# M632X.net
KiCad netlist of a schematic drawn in EAGLE
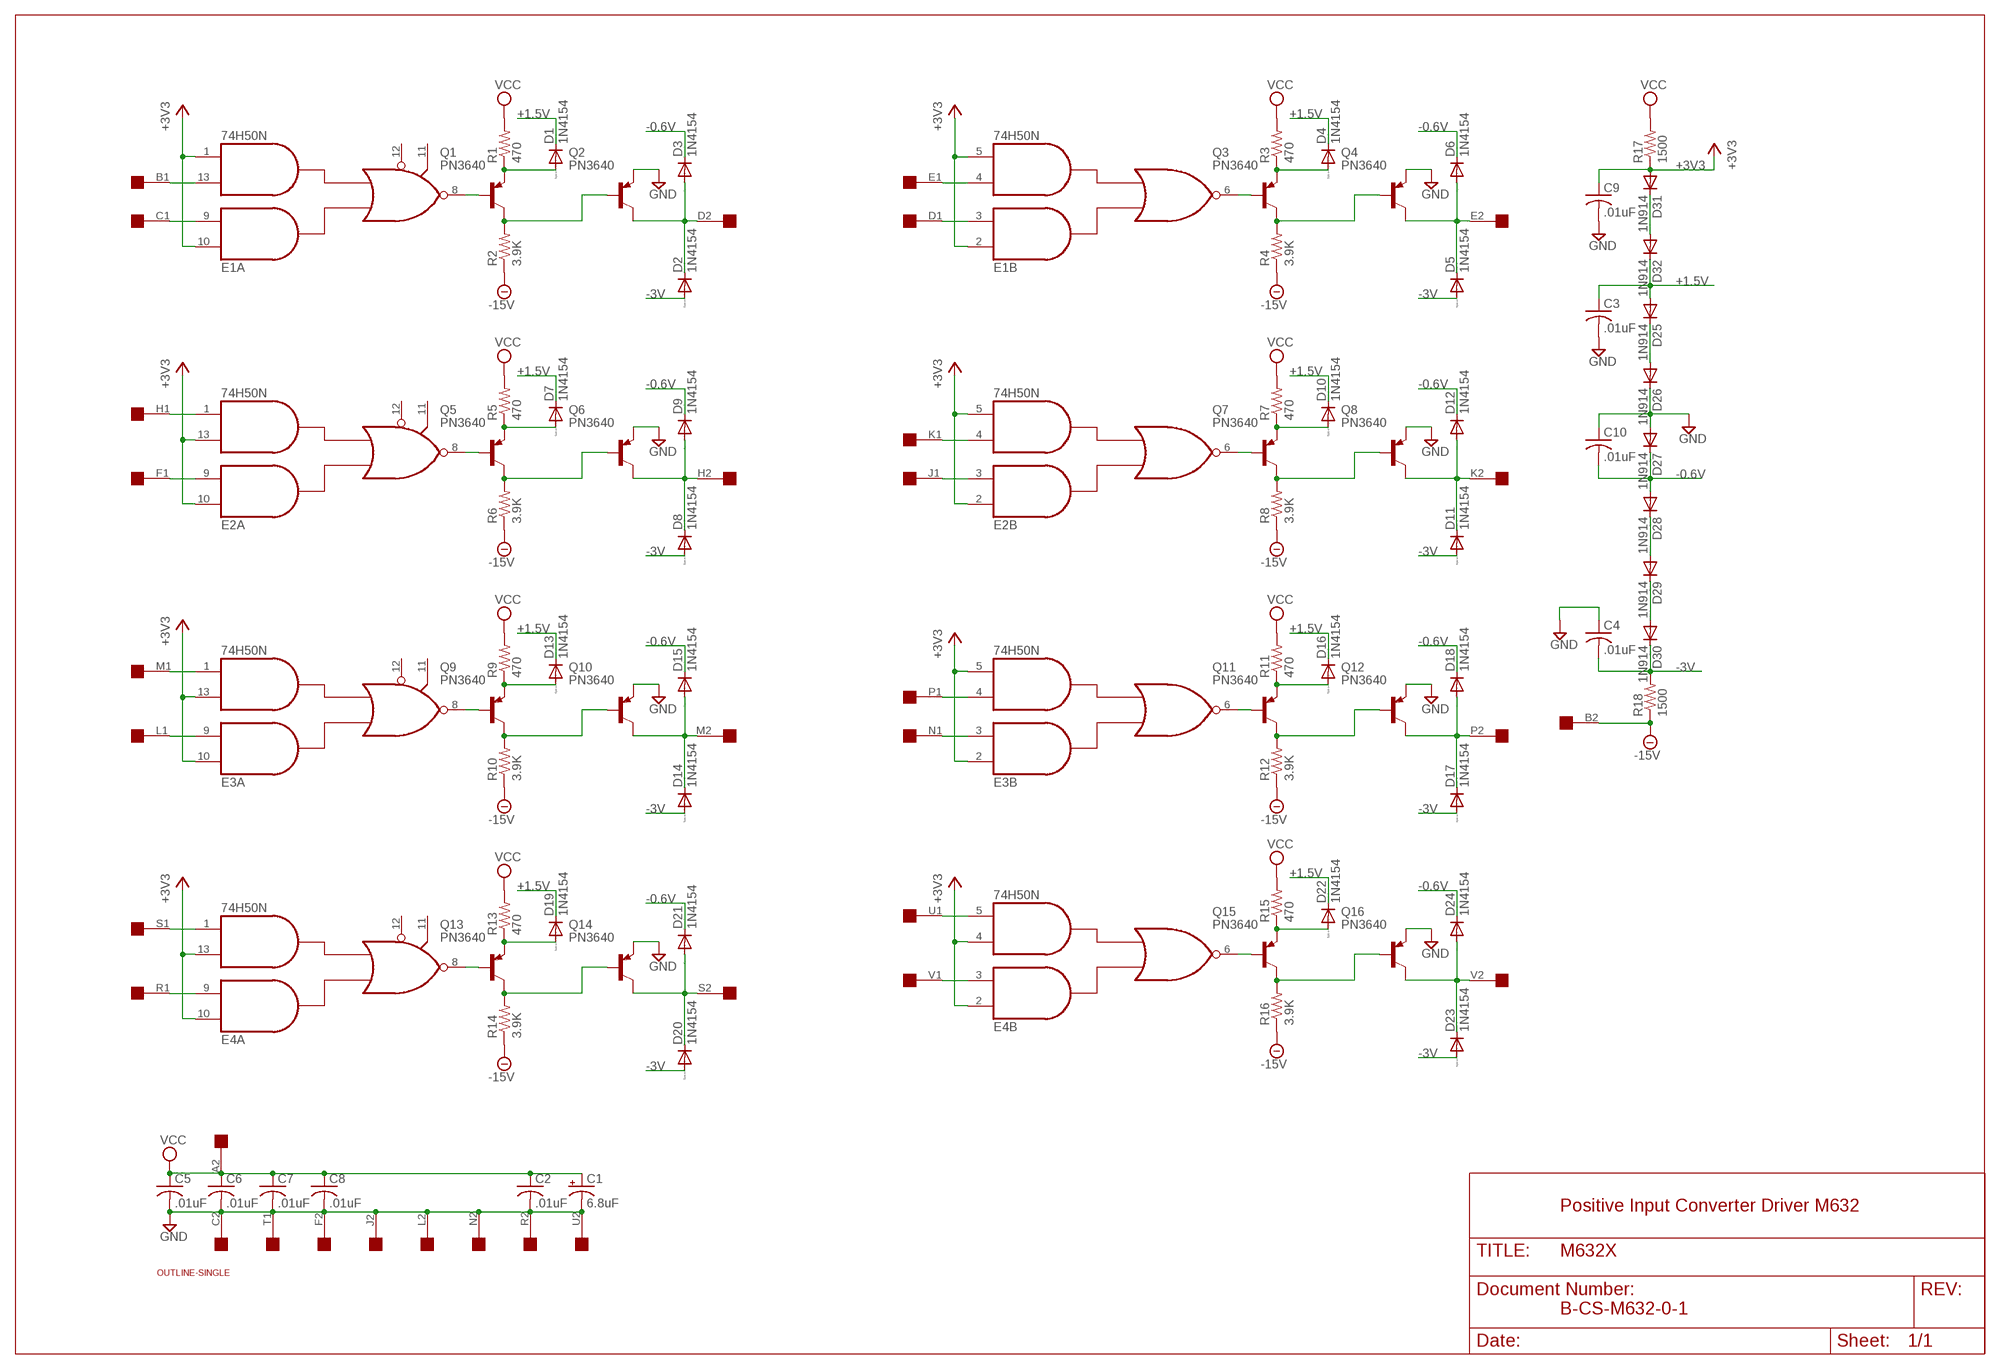
[diagram p0: schematic, sheet 1]

(export (version "E")
  (design (tool "Eeschema 10.0.6"))
  (components
    (comp (ref "C1")
      (value "6.8uF")
      (footprint "eagle-import:E12-8")
      (libsource (lib "eagle-import") (part "CPOL-USE20-8AXIAL"))
    )
    (comp (ref "C2")
      (value ".01uF")
      (footprint "eagle-import:C050-025X075")
      (libsource (lib "eagle-import") (part "C-US050-025X075"))
    )
    (comp (ref "C3")
      (value ".01uF")
      (footprint "eagle-import:C050-025X075")
      (libsource (lib "eagle-import") (part "C-US050-025X075"))
    )
    (comp (ref "C4")
      (value ".01uF")
      (footprint "eagle-import:C050-025X075")
      (libsource (lib "eagle-import") (part "C-US050-025X075"))
    )
    (comp (ref "C5")
      (value ".01uF")
      (footprint "eagle-import:C050-025X075")
      (libsource (lib "eagle-import") (part "C-US050-025X075"))
    )
    (comp (ref "C6")
      (value ".01uF")
      (footprint "eagle-import:C050-025X075")
      (libsource (lib "eagle-import") (part "C-US050-025X075"))
    )
    (comp (ref "C7")
      (value ".01uF")
      (footprint "eagle-import:C050-025X075")
      (libsource (lib "eagle-import") (part "C-US050-025X075"))
    )
    (comp (ref "C8")
      (value ".01uF")
      (footprint "eagle-import:C050-025X075")
      (libsource (lib "eagle-import") (part "C-US050-025X075"))
    )
    (comp (ref "C9")
      (value ".01uF")
      (footprint "eagle-import:C050-025X075")
      (libsource (lib "eagle-import") (part "C-US050-025X075"))
    )
    (comp (ref "C10")
      (value ".01uF")
      (footprint "eagle-import:C050-025X075")
      (libsource (lib "eagle-import") (part "C-US050-025X075"))
    )
    (comp (ref "D1")
      (value "1N4154")
      (footprint "eagle-import:DO35-10")
      (libsource (lib "eagle-import") (part "1N4148DO35-10"))
    )
    (comp (ref "D2")
      (value "1N4154")
      (footprint "eagle-import:DO35-10")
      (libsource (lib "eagle-import") (part "1N4148DO35-10"))
    )
    (comp (ref "D3")
      (value "1N4154")
      (footprint "eagle-import:DO35-10")
      (libsource (lib "eagle-import") (part "1N4148DO35-10"))
    )
    (comp (ref "D4")
      (value "1N4154")
      (footprint "eagle-import:DO35-10")
      (libsource (lib "eagle-import") (part "1N4148DO35-10"))
    )
    (comp (ref "D5")
      (value "1N4154")
      (footprint "eagle-import:DO35-10")
      (libsource (lib "eagle-import") (part "1N4148DO35-10"))
    )
    (comp (ref "D6")
      (value "1N4154")
      (footprint "eagle-import:DO35-10")
      (libsource (lib "eagle-import") (part "1N4148DO35-10"))
    )
    (comp (ref "D7")
      (value "1N4154")
      (footprint "eagle-import:DO35-10")
      (libsource (lib "eagle-import") (part "1N4148DO35-10"))
    )
    (comp (ref "D8")
      (value "1N4154")
      (footprint "eagle-import:DO35-10")
      (libsource (lib "eagle-import") (part "1N4148DO35-10"))
    )
    (comp (ref "D9")
      (value "1N4154")
      (footprint "eagle-import:DO35-10")
      (libsource (lib "eagle-import") (part "1N4148DO35-10"))
    )
    (comp (ref "D10")
      (value "1N4154")
      (footprint "eagle-import:DO35-10")
      (libsource (lib "eagle-import") (part "1N4148DO35-10"))
    )
    (comp (ref "D11")
      (value "1N4154")
      (footprint "eagle-import:DO35-10")
      (libsource (lib "eagle-import") (part "1N4148DO35-10"))
    )
    (comp (ref "D12")
      (value "1N4154")
      (footprint "eagle-import:DO35-10")
      (libsource (lib "eagle-import") (part "1N4148DO35-10"))
    )
    (comp (ref "D13")
      (value "1N4154")
      (footprint "eagle-import:DO35-10")
      (libsource (lib "eagle-import") (part "1N4148DO35-10"))
    )
    (comp (ref "D14")
      (value "1N4154")
      (footprint "eagle-import:DO35-10")
      (libsource (lib "eagle-import") (part "1N4148DO35-10"))
    )
    (comp (ref "D15")
      (value "1N4154")
      (footprint "eagle-import:DO35-10")
      (libsource (lib "eagle-import") (part "1N4148DO35-10"))
    )
    (comp (ref "D16")
      (value "1N4154")
      (footprint "eagle-import:DO35-10")
      (libsource (lib "eagle-import") (part "1N4148DO35-10"))
    )
    (comp (ref "D17")
      (value "1N4154")
      (footprint "eagle-import:DO35-10")
      (libsource (lib "eagle-import") (part "1N4148DO35-10"))
    )
    (comp (ref "D18")
      (value "1N4154")
      (footprint "eagle-import:DO35-10")
      (libsource (lib "eagle-import") (part "1N4148DO35-10"))
    )
    (comp (ref "D19")
      (value "1N4154")
      (footprint "eagle-import:DO35-10")
      (libsource (lib "eagle-import") (part "1N4148DO35-10"))
    )
    (comp (ref "D20")
      (value "1N4154")
      (footprint "eagle-import:DO35-10")
      (libsource (lib "eagle-import") (part "1N4148DO35-10"))
    )
    (comp (ref "D21")
      (value "1N4154")
      (footprint "eagle-import:DO35-10")
      (libsource (lib "eagle-import") (part "1N4148DO35-10"))
    )
    (comp (ref "D22")
      (value "1N4154")
      (footprint "eagle-import:DO35-10")
      (libsource (lib "eagle-import") (part "1N4148DO35-10"))
    )
    (comp (ref "D23")
      (value "1N4154")
      (footprint "eagle-import:DO35-10")
      (libsource (lib "eagle-import") (part "1N4148DO35-10"))
    )
    (comp (ref "D24")
      (value "1N4154")
      (footprint "eagle-import:DO35-10")
      (libsource (lib "eagle-import") (part "1N4148DO35-10"))
    )
    (comp (ref "D25")
      (value "1N914")
      (footprint "eagle-import:DO35-10")
      (libsource (lib "eagle-import") (part "1N4148DO35-10"))
    )
    (comp (ref "D26")
      (value "1N914")
      (footprint "eagle-import:DO35-10")
      (libsource (lib "eagle-import") (part "1N4148DO35-10"))
    )
    (comp (ref "D27")
      (value "1N914")
      (footprint "eagle-import:DO35-10")
      (libsource (lib "eagle-import") (part "1N4148DO35-10"))
    )
    (comp (ref "D28")
      (value "1N914")
      (footprint "eagle-import:DO35-10")
      (libsource (lib "eagle-import") (part "1N4148DO35-10"))
    )
    (comp (ref "D29")
      (value "1N914")
      (footprint "eagle-import:DO35-10")
      (libsource (lib "eagle-import") (part "1N4148DO35-10"))
    )
    (comp (ref "D30")
      (value "1N914")
      (footprint "eagle-import:DO35-10")
      (libsource (lib "eagle-import") (part "1N4148DO35-10"))
    )
    (comp (ref "D31")
      (value "1N914")
      (footprint "eagle-import:DO35-10")
      (libsource (lib "eagle-import") (part "1N4148DO35-10"))
    )
    (comp (ref "D32")
      (value "1N914")
      (footprint "eagle-import:DO35-10")
      (libsource (lib "eagle-import") (part "1N4148DO35-10"))
    )
    (comp (ref "E1")
      (value "74H50N")
      (footprint "eagle-import:DIL14")
      (libsource (lib "eagle-import") (part "7450N"))
    )
    (comp (ref "E2")
      (value "74H50N")
      (footprint "eagle-import:DIL14")
      (libsource (lib "eagle-import") (part "7450N"))
    )
    (comp (ref "E3")
      (value "74H50N")
      (footprint "eagle-import:DIL14")
      (libsource (lib "eagle-import") (part "7450N"))
    )
    (comp (ref "E4")
      (value "74H50N")
      (footprint "eagle-import:DIL14")
      (libsource (lib "eagle-import") (part "7450N"))
    )
    (comp (ref "Q1")
      (value "PN3640")
      (footprint "eagle-import:TO39")
      (libsource (lib "eagle-import") (part "2N2904"))
    )
    (comp (ref "Q2")
      (value "PN3640")
      (footprint "eagle-import:TO39")
      (libsource (lib "eagle-import") (part "2N2904"))
    )
    (comp (ref "Q3")
      (value "PN3640")
      (footprint "eagle-import:TO39")
      (libsource (lib "eagle-import") (part "2N2904"))
    )
    (comp (ref "Q4")
      (value "PN3640")
      (footprint "eagle-import:TO39")
      (libsource (lib "eagle-import") (part "2N2904"))
    )
    (comp (ref "Q5")
      (value "PN3640")
      (footprint "eagle-import:TO39")
      (libsource (lib "eagle-import") (part "2N2904"))
    )
    (comp (ref "Q6")
      (value "PN3640")
      (footprint "eagle-import:TO39")
      (libsource (lib "eagle-import") (part "2N2904"))
    )
    (comp (ref "Q7")
      (value "PN3640")
      (footprint "eagle-import:TO39")
      (libsource (lib "eagle-import") (part "2N2904"))
    )
    (comp (ref "Q8")
      (value "PN3640")
      (footprint "eagle-import:TO39")
      (libsource (lib "eagle-import") (part "2N2904"))
    )
    (comp (ref "Q9")
      (value "PN3640")
      (footprint "eagle-import:TO39")
      (libsource (lib "eagle-import") (part "2N2904"))
    )
    (comp (ref "Q10")
      (value "PN3640")
      (footprint "eagle-import:TO39")
      (libsource (lib "eagle-import") (part "2N2904"))
    )
    (comp (ref "Q11")
      (value "PN3640")
      (footprint "eagle-import:TO39")
      (libsource (lib "eagle-import") (part "2N2904"))
    )
    (comp (ref "Q12")
      (value "PN3640")
      (footprint "eagle-import:TO39")
      (libsource (lib "eagle-import") (part "2N2904"))
    )
    (comp (ref "Q13")
      (value "PN3640")
      (footprint "eagle-import:TO39")
      (libsource (lib "eagle-import") (part "2N2904"))
    )
    (comp (ref "Q14")
      (value "PN3640")
      (footprint "eagle-import:TO39")
      (libsource (lib "eagle-import") (part "2N2904"))
    )
    (comp (ref "Q15")
      (value "PN3640")
      (footprint "eagle-import:TO39")
      (libsource (lib "eagle-import") (part "2N2904"))
    )
    (comp (ref "Q16")
      (value "PN3640")
      (footprint "eagle-import:TO39")
      (libsource (lib "eagle-import") (part "2N2904"))
    )
    (comp (ref "R1")
      (value "470")
      (footprint "eagle-import:0207_10")
      (libsource (lib "eagle-import") (part "R-US_0207/10"))
    )
    (comp (ref "R2")
      (value "3.9K")
      (footprint "eagle-import:0207_10")
      (libsource (lib "eagle-import") (part "R-US_0207/10"))
    )
    (comp (ref "R3")
      (value "470")
      (footprint "eagle-import:0207_10")
      (libsource (lib "eagle-import") (part "R-US_0207/10"))
    )
    (comp (ref "R4")
      (value "3.9K")
      (footprint "eagle-import:0207_10")
      (libsource (lib "eagle-import") (part "R-US_0207/10"))
    )
    (comp (ref "R5")
      (value "470")
      (footprint "eagle-import:0207_10")
      (libsource (lib "eagle-import") (part "R-US_0207/10"))
    )
    (comp (ref "R6")
      (value "3.9K")
      (footprint "eagle-import:0207_10")
      (libsource (lib "eagle-import") (part "R-US_0207/10"))
    )
    (comp (ref "R7")
      (value "470")
      (footprint "eagle-import:0207_10")
      (libsource (lib "eagle-import") (part "R-US_0207/10"))
    )
    (comp (ref "R8")
      (value "3.9K")
      (footprint "eagle-import:0207_10")
      (libsource (lib "eagle-import") (part "R-US_0207/10"))
    )
    (comp (ref "R9")
      (value "470")
      (footprint "eagle-import:0207_10")
      (libsource (lib "eagle-import") (part "R-US_0207/10"))
    )
    (comp (ref "R10")
      (value "3.9K")
      (footprint "eagle-import:0207_10")
      (libsource (lib "eagle-import") (part "R-US_0207/10"))
    )
    (comp (ref "R11")
      (value "470")
      (footprint "eagle-import:0207_10")
      (libsource (lib "eagle-import") (part "R-US_0207/10"))
    )
    (comp (ref "R12")
      (value "3.9K")
      (footprint "eagle-import:0207_10")
      (libsource (lib "eagle-import") (part "R-US_0207/10"))
    )
    (comp (ref "R13")
      (value "470")
      (footprint "eagle-import:0207_10")
      (libsource (lib "eagle-import") (part "R-US_0207/10"))
    )
    (comp (ref "R14")
      (value "3.9K")
      (footprint "eagle-import:0207_10")
      (libsource (lib "eagle-import") (part "R-US_0207/10"))
    )
    (comp (ref "R15")
      (value "470")
      (footprint "eagle-import:0207_10")
      (libsource (lib "eagle-import") (part "R-US_0207/10"))
    )
    (comp (ref "R16")
      (value "3.9K")
      (footprint "eagle-import:0207_10")
      (libsource (lib "eagle-import") (part "R-US_0207/10"))
    )
    (comp (ref "R17")
      (value "1500")
      (footprint "eagle-import:0207_10")
      (libsource (lib "eagle-import") (part "R-US_0207/10"))
    )
    (comp (ref "R18")
      (value "1500")
      (footprint "eagle-import:0207_10")
      (libsource (lib "eagle-import") (part "R-US_0207/10"))
    )
    (comp (ref "U$1")
      (value "SINGLE")
      (footprint "eagle-import:EDGE-CON2")
      (libsource (lib "eagle-import") (part "SINGLE"))
    )
    (comp (ref "U$4")
      (value "OUTLINE-SINGLE")
      (footprint "eagle-import:SINGLE")
      (libsource (lib "eagle-import") (part "OUTLINE-SINGLE"))
    )
  )
  (nets
    (net (code "1") (name "+3V3") (class "Default")
      (node (ref "C9") (pin "1") (pinfunction "1_1") (pintype "passive"))
      (node (ref "D31") (pin "A") (pinfunction "A_A") (pintype "passive"))
      (node (ref "E1") (pin "1") (pinfunction "I4_1") (pintype "input"))
      (node (ref "E1") (pin "10") (pinfunction "I1_10") (pintype "input"))
      (node (ref "E1") (pin "2") (pinfunction "I1_2") (pintype "input"))
      (node (ref "E1") (pin "5") (pinfunction "I4_5") (pintype "input"))
      (node (ref "E2") (pin "10") (pinfunction "I1_10") (pintype "input"))
      (node (ref "E2") (pin "13") (pinfunction "I3_13") (pintype "input"))
      (node (ref "E2") (pin "2") (pinfunction "I1_2") (pintype "input"))
      (node (ref "E2") (pin "5") (pinfunction "I4_5") (pintype "input"))
      (node (ref "E3") (pin "10") (pinfunction "I1_10") (pintype "input"))
      (node (ref "E3") (pin "13") (pinfunction "I3_13") (pintype "input"))
      (node (ref "E3") (pin "2") (pinfunction "I1_2") (pintype "input"))
      (node (ref "E3") (pin "5") (pinfunction "I4_5") (pintype "input"))
      (node (ref "E4") (pin "10") (pinfunction "I1_10") (pintype "input"))
      (node (ref "E4") (pin "13") (pinfunction "I3_13") (pintype "input"))
      (node (ref "E4") (pin "2") (pinfunction "I1_2") (pintype "input"))
      (node (ref "E4") (pin "4") (pinfunction "I3_4") (pintype "input"))
      (node (ref "R17") (pin "1") (pinfunction "1_1") (pintype "passive"))
    )
    (net (code "2") (name "-15V") (class "Default")
      (node (ref "R10") (pin "1") (pinfunction "1_1") (pintype "passive"))
      (node (ref "R12") (pin "1") (pinfunction "1_1") (pintype "passive"))
      (node (ref "R14") (pin "1") (pinfunction "1_1") (pintype "passive"))
      (node (ref "R16") (pin "1") (pinfunction "1_1") (pintype "passive"))
      (node (ref "R18") (pin "1") (pinfunction "1_1") (pintype "passive"))
      (node (ref "R2") (pin "1") (pinfunction "1_1") (pintype "passive"))
      (node (ref "R4") (pin "1") (pinfunction "1_1") (pintype "passive"))
      (node (ref "R6") (pin "1") (pinfunction "1_1") (pintype "passive"))
      (node (ref "R8") (pin "1") (pinfunction "1_1") (pintype "passive"))
      (node (ref "U$1") (pin "B2") (pinfunction "1_B2") (pintype "bidirectional"))
    )
    (net (code "3") (name "/+1.5V") (class "Default")
      (node (ref "C3") (pin "1") (pinfunction "1_1") (pintype "passive"))
      (node (ref "D1") (pin "C") (pinfunction "C_C") (pintype "passive"))
      (node (ref "D10") (pin "C") (pinfunction "C_C") (pintype "passive"))
      (node (ref "D13") (pin "C") (pinfunction "C_C") (pintype "passive"))
      (node (ref "D16") (pin "C") (pinfunction "C_C") (pintype "passive"))
      (node (ref "D19") (pin "C") (pinfunction "C_C") (pintype "passive"))
      (node (ref "D22") (pin "C") (pinfunction "C_C") (pintype "passive"))
      (node (ref "D25") (pin "A") (pinfunction "A_A") (pintype "passive"))
      (node (ref "D32") (pin "C") (pinfunction "C_C") (pintype "passive"))
      (node (ref "D4") (pin "C") (pinfunction "C_C") (pintype "passive"))
      (node (ref "D7") (pin "C") (pinfunction "C_C") (pintype "passive"))
    )
    (net (code "4") (name "/-0.6V") (class "Default")
      (node (ref "C10") (pin "2") (pinfunction "2_2") (pintype "passive"))
      (node (ref "D12") (pin "C") (pinfunction "C_C") (pintype "passive"))
      (node (ref "D15") (pin "C") (pinfunction "C_C") (pintype "passive"))
      (node (ref "D18") (pin "C") (pinfunction "C_C") (pintype "passive"))
      (node (ref "D21") (pin "C") (pinfunction "C_C") (pintype "passive"))
      (node (ref "D24") (pin "C") (pinfunction "C_C") (pintype "passive"))
      (node (ref "D27") (pin "C") (pinfunction "C_C") (pintype "passive"))
      (node (ref "D28") (pin "A") (pinfunction "A_A") (pintype "passive"))
      (node (ref "D3") (pin "C") (pinfunction "C_C") (pintype "passive"))
      (node (ref "D6") (pin "C") (pinfunction "C_C") (pintype "passive"))
      (node (ref "D9") (pin "C") (pinfunction "C_C") (pintype "passive"))
    )
    (net (code "5") (name "/-3V") (class "Default")
      (node (ref "C4") (pin "2") (pinfunction "2_2") (pintype "passive"))
      (node (ref "D11") (pin "A") (pinfunction "A_A") (pintype "passive"))
      (node (ref "D14") (pin "A") (pinfunction "A_A") (pintype "passive"))
      (node (ref "D17") (pin "A") (pinfunction "A_A") (pintype "passive"))
      (node (ref "D2") (pin "A") (pinfunction "A_A") (pintype "passive"))
      (node (ref "D20") (pin "A") (pinfunction "A_A") (pintype "passive"))
      (node (ref "D23") (pin "A") (pinfunction "A_A") (pintype "passive"))
      (node (ref "D30") (pin "C") (pinfunction "C_C") (pintype "passive"))
      (node (ref "D5") (pin "A") (pinfunction "A_A") (pintype "passive"))
      (node (ref "D8") (pin "A") (pinfunction "A_A") (pintype "passive"))
      (node (ref "R18") (pin "2") (pinfunction "2_2") (pintype "passive"))
    )
    (net (code "6") (name "GND") (class "Default")
      (node (ref "C1") (pin "-") (pinfunction "-_-") (pintype "passive"))
      (node (ref "C10") (pin "1") (pinfunction "1_1") (pintype "passive"))
      (node (ref "C2") (pin "2") (pinfunction "2_2") (pintype "passive"))
      (node (ref "C3") (pin "2") (pinfunction "2_2") (pintype "passive"))
      (node (ref "C4") (pin "1") (pinfunction "1_1") (pintype "passive"))
      (node (ref "C5") (pin "2") (pinfunction "2_2") (pintype "passive"))
      (node (ref "C6") (pin "2") (pinfunction "2_2") (pintype "passive"))
      (node (ref "C7") (pin "2") (pinfunction "2_2") (pintype "passive"))
      (node (ref "C8") (pin "2") (pinfunction "2_2") (pintype "passive"))
      (node (ref "C9") (pin "2") (pinfunction "2_2") (pintype "passive"))
      (node (ref "D26") (pin "C") (pinfunction "C_C") (pintype "passive"))
      (node (ref "D27") (pin "A") (pinfunction "A_A") (pintype "passive"))
      (node (ref "Q10") (pin "1") (pinfunction "E_1") (pintype "passive"))
      (node (ref "Q12") (pin "1") (pinfunction "E_1") (pintype "passive"))
      (node (ref "Q14") (pin "1") (pinfunction "E_1") (pintype "passive"))
      (node (ref "Q16") (pin "1") (pinfunction "E_1") (pintype "passive"))
      (node (ref "Q2") (pin "1") (pinfunction "E_1") (pintype "passive"))
      (node (ref "Q4") (pin "1") (pinfunction "E_1") (pintype "passive"))
      (node (ref "Q6") (pin "1") (pinfunction "E_1") (pintype "passive"))
      (node (ref "Q8") (pin "1") (pinfunction "E_1") (pintype "passive"))
      (node (ref "U$1") (pin "C2") (pinfunction "1_C2") (pintype "bidirectional"))
      (node (ref "U$1") (pin "F2") (pinfunction "1_F2") (pintype "bidirectional"))
      (node (ref "U$1") (pin "J2") (pinfunction "1_J2") (pintype "bidirectional"))
      (node (ref "U$1") (pin "L2") (pinfunction "1_L2") (pintype "bidirectional"))
      (node (ref "U$1") (pin "N2") (pinfunction "1_N2") (pintype "bidirectional"))
      (node (ref "U$1") (pin "R2") (pinfunction "1_R2") (pintype "bidirectional"))
      (node (ref "U$1") (pin "T1") (pinfunction "1_T1") (pintype "bidirectional"))
      (node (ref "U$1") (pin "U2") (pinfunction "1_U2") (pintype "bidirectional"))
    )
    (net (code "7") (name "Net-(D25-PadC)") (class "Default")
      (node (ref "D25") (pin "C") (pinfunction "C_C") (pintype "passive"))
      (node (ref "D26") (pin "A") (pinfunction "A_A") (pintype "passive"))
    )
    (net (code "8") (name "Net-(D28-PadC)") (class "Default")
      (node (ref "D28") (pin "C") (pinfunction "C_C") (pintype "passive"))
      (node (ref "D29") (pin "A") (pinfunction "A_A") (pintype "passive"))
    )
    (net (code "9") (name "Net-(D29-PadC)") (class "Default")
      (node (ref "D29") (pin "C") (pinfunction "C_C") (pintype "passive"))
      (node (ref "D30") (pin "A") (pinfunction "A_A") (pintype "passive"))
    )
    (net (code "10") (name "Net-(D31-PadC)") (class "Default")
      (node (ref "D31") (pin "C") (pinfunction "C_C") (pintype "passive"))
      (node (ref "D32") (pin "A") (pinfunction "A_A") (pintype "passive"))
    )
    (net (code "11") (name "Net-(E1A-I2)") (class "Default")
      (node (ref "E1") (pin "9") (pinfunction "I2_9") (pintype "input"))
      (node (ref "U$1") (pin "C1") (pinfunction "1_C1") (pintype "bidirectional"))
    )
    (net (code "12") (name "Net-(E1A-I3)") (class "Default")
      (node (ref "E1") (pin "13") (pinfunction "I3_13") (pintype "input"))
      (node (ref "U$1") (pin "B1") (pinfunction "1_B1") (pintype "bidirectional"))
    )
    (net (code "13") (name "Net-(E1A-O)") (class "Default")
      (node (ref "E1") (pin "8") (pinfunction "O_8") (pintype "output"))
      (node (ref "Q1") (pin "2") (pinfunction "B_2") (pintype "passive"))
    )
    (net (code "14") (name "Net-(E1B-I2)") (class "Default")
      (node (ref "E1") (pin "3") (pinfunction "I2_3") (pintype "input"))
      (node (ref "U$1") (pin "D1") (pinfunction "1_D1") (pintype "bidirectional"))
    )
    (net (code "15") (name "Net-(E1B-I3)") (class "Default")
      (node (ref "E1") (pin "4") (pinfunction "I3_4") (pintype "input"))
      (node (ref "U$1") (pin "E1") (pinfunction "1_E1") (pintype "bidirectional"))
    )
    (net (code "16") (name "Net-(E1B-O)") (class "Default")
      (node (ref "E1") (pin "6") (pinfunction "O_6") (pintype "output"))
      (node (ref "Q3") (pin "2") (pinfunction "B_2") (pintype "passive"))
    )
    (net (code "17") (name "Net-(E2A-I2)") (class "Default")
      (node (ref "E2") (pin "9") (pinfunction "I2_9") (pintype "input"))
      (node (ref "U$1") (pin "F1") (pinfunction "1_F1") (pintype "bidirectional"))
    )
    (net (code "18") (name "Net-(E2A-I4)") (class "Default")
      (node (ref "E2") (pin "1") (pinfunction "I4_1") (pintype "input"))
      (node (ref "U$1") (pin "H1") (pinfunction "1_H1") (pintype "bidirectional"))
    )
    (net (code "19") (name "Net-(E2A-O)") (class "Default")
      (node (ref "E2") (pin "8") (pinfunction "O_8") (pintype "output"))
      (node (ref "Q5") (pin "2") (pinfunction "B_2") (pintype "passive"))
    )
    (net (code "20") (name "Net-(E2B-I2)") (class "Default")
      (node (ref "E2") (pin "3") (pinfunction "I2_3") (pintype "input"))
      (node (ref "U$1") (pin "J1") (pinfunction "1_J1") (pintype "bidirectional"))
    )
    (net (code "21") (name "Net-(E2B-I3)") (class "Default")
      (node (ref "E2") (pin "4") (pinfunction "I3_4") (pintype "input"))
      (node (ref "U$1") (pin "K1") (pinfunction "1_K1") (pintype "bidirectional"))
    )
    (net (code "22") (name "Net-(E2B-O)") (class "Default")
      (node (ref "E2") (pin "6") (pinfunction "O_6") (pintype "output"))
      (node (ref "Q7") (pin "2") (pinfunction "B_2") (pintype "passive"))
    )
    (net (code "23") (name "Net-(E3A-I2)") (class "Default")
      (node (ref "E3") (pin "9") (pinfunction "I2_9") (pintype "input"))
      (node (ref "U$1") (pin "L1") (pinfunction "1_L1") (pintype "bidirectional"))
    )
    (net (code "24") (name "Net-(E3A-I4)") (class "Default")
      (node (ref "E3") (pin "1") (pinfunction "I4_1") (pintype "input"))
      (node (ref "U$1") (pin "M1") (pinfunction "1_M1") (pintype "bidirectional"))
    )
    (net (code "25") (name "Net-(E3A-O)") (class "Default")
      (node (ref "E3") (pin "8") (pinfunction "O_8") (pintype "output"))
      (node (ref "Q9") (pin "2") (pinfunction "B_2") (pintype "passive"))
    )
    (net (code "26") (name "Net-(E3B-I2)") (class "Default")
      (node (ref "E3") (pin "3") (pinfunction "I2_3") (pintype "input"))
      (node (ref "U$1") (pin "N1") (pinfunction "1_N1") (pintype "bidirectional"))
    )
    (net (code "27") (name "Net-(E3B-I3)") (class "Default")
      (node (ref "E3") (pin "4") (pinfunction "I3_4") (pintype "input"))
      (node (ref "U$1") (pin "P1") (pinfunction "1_P1") (pintype "bidirectional"))
    )
    (net (code "28") (name "Net-(E3B-O)") (class "Default")
      (node (ref "E3") (pin "6") (pinfunction "O_6") (pintype "output"))
      (node (ref "Q11") (pin "2") (pinfunction "B_2") (pintype "passive"))
    )
    (net (code "29") (name "Net-(E4A-I2)") (class "Default")
      (node (ref "E4") (pin "9") (pinfunction "I2_9") (pintype "input"))
      (node (ref "U$1") (pin "R1") (pinfunction "1_R1") (pintype "bidirectional"))
    )
    (net (code "30") (name "Net-(E4A-I4)") (class "Default")
      (node (ref "E4") (pin "1") (pinfunction "I4_1") (pintype "input"))
      (node (ref "U$1") (pin "S1") (pinfunction "1_S1") (pintype "bidirectional"))
    )
    (net (code "31") (name "Net-(E4A-O)") (class "Default")
      (node (ref "E4") (pin "8") (pinfunction "O_8") (pintype "output"))
      (node (ref "Q13") (pin "2") (pinfunction "B_2") (pintype "passive"))
    )
    (net (code "32") (name "Net-(E4B-I2)") (class "Default")
      (node (ref "E4") (pin "3") (pinfunction "I2_3") (pintype "input"))
      (node (ref "U$1") (pin "V1") (pinfunction "1_V1") (pintype "bidirectional"))
    )
    (net (code "33") (name "Net-(E4B-I4)") (class "Default")
      (node (ref "E4") (pin "5") (pinfunction "I4_5") (pintype "input"))
      (node (ref "U$1") (pin "U1") (pinfunction "1_U1") (pintype "bidirectional"))
    )
    (net (code "34") (name "Net-(E4B-O)") (class "Default")
      (node (ref "E4") (pin "6") (pinfunction "O_6") (pintype "output"))
      (node (ref "Q15") (pin "2") (pinfunction "B_2") (pintype "passive"))
    )
    (net (code "35") (name "Net-(Q1-C)") (class "Default")
      (node (ref "Q1") (pin "3") (pinfunction "C_3") (pintype "passive"))
      (node (ref "Q2") (pin "2") (pinfunction "B_2") (pintype "passive"))
      (node (ref "R2") (pin "2") (pinfunction "2_2") (pintype "passive"))
    )
    (net (code "36") (name "Net-(Q1-E)") (class "Default")
      (node (ref "D1") (pin "A") (pinfunction "A_A") (pintype "passive"))
      (node (ref "Q1") (pin "1") (pinfunction "E_1") (pintype "passive"))
      (node (ref "R1") (pin "1") (pinfunction "1_1") (pintype "passive"))
    )
    (net (code "37") (name "Net-(Q2-C)") (class "Default")
      (node (ref "D2") (pin "C") (pinfunction "C_C") (pintype "passive"))
      (node (ref "D3") (pin "A") (pinfunction "A_A") (pintype "passive"))
      (node (ref "Q2") (pin "3") (pinfunction "C_3") (pintype "passive"))
      (node (ref "U$1") (pin "D2") (pinfunction "1_D2") (pintype "bidirectional"))
    )
    (net (code "38") (name "Net-(Q3-C)") (class "Default")
      (node (ref "Q3") (pin "3") (pinfunction "C_3") (pintype "passive"))
      (node (ref "Q4") (pin "2") (pinfunction "B_2") (pintype "passive"))
      (node (ref "R4") (pin "2") (pinfunction "2_2") (pintype "passive"))
    )
    (net (code "39") (name "Net-(Q3-E)") (class "Default")
      (node (ref "D4") (pin "A") (pinfunction "A_A") (pintype "passive"))
      (node (ref "Q3") (pin "1") (pinfunction "E_1") (pintype "passive"))
      (node (ref "R3") (pin "1") (pinfunction "1_1") (pintype "passive"))
    )
    (net (code "40") (name "Net-(Q4-C)") (class "Default")
      (node (ref "D5") (pin "C") (pinfunction "C_C") (pintype "passive"))
      (node (ref "D6") (pin "A") (pinfunction "A_A") (pintype "passive"))
      (node (ref "Q4") (pin "3") (pinfunction "C_3") (pintype "passive"))
      (node (ref "U$1") (pin "E2") (pinfunction "1_E2") (pintype "bidirectional"))
    )
    (net (code "41") (name "Net-(Q5-C)") (class "Default")
      (node (ref "Q5") (pin "3") (pinfunction "C_3") (pintype "passive"))
      (node (ref "Q6") (pin "2") (pinfunction "B_2") (pintype "passive"))
      (node (ref "R6") (pin "2") (pinfunction "2_2") (pintype "passive"))
    )
    (net (code "42") (name "Net-(Q5-E)") (class "Default")
      (node (ref "D7") (pin "A") (pinfunction "A_A") (pintype "passive"))
      (node (ref "Q5") (pin "1") (pinfunction "E_1") (pintype "passive"))
      (node (ref "R5") (pin "1") (pinfunction "1_1") (pintype "passive"))
    )
    (net (code "43") (name "Net-(Q6-C)") (class "Default")
      (node (ref "D8") (pin "C") (pinfunction "C_C") (pintype "passive"))
      (node (ref "D9") (pin "A") (pinfunction "A_A") (pintype "passive"))
      (node (ref "Q6") (pin "3") (pinfunction "C_3") (pintype "passive"))
      (node (ref "U$1") (pin "H2") (pinfunction "1_H2") (pintype "bidirectional"))
    )
    (net (code "44") (name "Net-(Q7-C)") (class "Default")
      (node (ref "Q7") (pin "3") (pinfunction "C_3") (pintype "passive"))
      (node (ref "Q8") (pin "2") (pinfunction "B_2") (pintype "passive"))
      (node (ref "R8") (pin "2") (pinfunction "2_2") (pintype "passive"))
    )
    (net (code "45") (name "Net-(Q7-E)") (class "Default")
      (node (ref "D10") (pin "A") (pinfunction "A_A") (pintype "passive"))
      (node (ref "Q7") (pin "1") (pinfunction "E_1") (pintype "passive"))
      (node (ref "R7") (pin "1") (pinfunction "1_1") (pintype "passive"))
    )
    (net (code "46") (name "Net-(Q8-C)") (class "Default")
      (node (ref "D11") (pin "C") (pinfunction "C_C") (pintype "passive"))
      (node (ref "D12") (pin "A") (pinfunction "A_A") (pintype "passive"))
      (node (ref "Q8") (pin "3") (pinfunction "C_3") (pintype "passive"))
      (node (ref "U$1") (pin "K2") (pinfunction "1_K2") (pintype "bidirectional"))
    )
    (net (code "47") (name "Net-(Q9-E)") (class "Default")
      (node (ref "D13") (pin "A") (pinfunction "A_A") (pintype "passive"))
      (node (ref "Q9") (pin "1") (pinfunction "E_1") (pintype "passive"))
      (node (ref "R9") (pin "1") (pinfunction "1_1") (pintype "passive"))
    )
    (net (code "48") (name "Net-(Q10-B)") (class "Default")
      (node (ref "Q10") (pin "2") (pinfunction "B_2") (pintype "passive"))
      (node (ref "Q9") (pin "3") (pinfunction "C_3") (pintype "passive"))
      (node (ref "R10") (pin "2") (pinfunction "2_2") (pintype "passive"))
    )
    (net (code "49") (name "Net-(Q10-C)") (class "Default")
      (node (ref "D14") (pin "C") (pinfunction "C_C") (pintype "passive"))
      (node (ref "D15") (pin "A") (pinfunction "A_A") (pintype "passive"))
      (node (ref "Q10") (pin "3") (pinfunction "C_3") (pintype "passive"))
      (node (ref "U$1") (pin "M2") (pinfunction "1_M2") (pintype "bidirectional"))
    )
    (net (code "50") (name "Net-(Q11-C)") (class "Default")
      (node (ref "Q11") (pin "3") (pinfunction "C_3") (pintype "passive"))
      (node (ref "Q12") (pin "2") (pinfunction "B_2") (pintype "passive"))
      (node (ref "R12") (pin "2") (pinfunction "2_2") (pintype "passive"))
    )
    (net (code "51") (name "Net-(Q11-E)") (class "Default")
      (node (ref "D16") (pin "A") (pinfunction "A_A") (pintype "passive"))
      (node (ref "Q11") (pin "1") (pinfunction "E_1") (pintype "passive"))
      (node (ref "R11") (pin "1") (pinfunction "1_1") (pintype "passive"))
    )
    (net (code "52") (name "Net-(Q12-C)") (class "Default")
      (node (ref "D17") (pin "C") (pinfunction "C_C") (pintype "passive"))
      (node (ref "D18") (pin "A") (pinfunction "A_A") (pintype "passive"))
      (node (ref "Q12") (pin "3") (pinfunction "C_3") (pintype "passive"))
      (node (ref "U$1") (pin "P2") (pinfunction "1_P2") (pintype "bidirectional"))
    )
    (net (code "53") (name "Net-(Q13-C)") (class "Default")
      (node (ref "Q13") (pin "3") (pinfunction "C_3") (pintype "passive"))
      (node (ref "Q14") (pin "2") (pinfunction "B_2") (pintype "passive"))
      (node (ref "R14") (pin "2") (pinfunction "2_2") (pintype "passive"))
    )
    (net (code "54") (name "Net-(Q13-E)") (class "Default")
      (node (ref "D19") (pin "A") (pinfunction "A_A") (pintype "passive"))
      (node (ref "Q13") (pin "1") (pinfunction "E_1") (pintype "passive"))
      (node (ref "R13") (pin "1") (pinfunction "1_1") (pintype "passive"))
    )
    (net (code "55") (name "Net-(Q14-C)") (class "Default")
      (node (ref "D20") (pin "C") (pinfunction "C_C") (pintype "passive"))
      (node (ref "D21") (pin "A") (pinfunction "A_A") (pintype "passive"))
      (node (ref "Q14") (pin "3") (pinfunction "C_3") (pintype "passive"))
      (node (ref "U$1") (pin "S2") (pinfunction "1_S2") (pintype "bidirectional"))
    )
    (net (code "56") (name "Net-(Q15-C)") (class "Default")
      (node (ref "Q15") (pin "3") (pinfunction "C_3") (pintype "passive"))
      (node (ref "Q16") (pin "2") (pinfunction "B_2") (pintype "passive"))
      (node (ref "R16") (pin "2") (pinfunction "2_2") (pintype "passive"))
    )
    (net (code "57") (name "Net-(Q15-E)") (class "Default")
      (node (ref "D22") (pin "A") (pinfunction "A_A") (pintype "passive"))
      (node (ref "Q15") (pin "1") (pinfunction "E_1") (pintype "passive"))
      (node (ref "R15") (pin "1") (pinfunction "1_1") (pintype "passive"))
    )
    (net (code "58") (name "Net-(Q16-C)") (class "Default")
      (node (ref "D23") (pin "C") (pinfunction "C_C") (pintype "passive"))
      (node (ref "D24") (pin "A") (pinfunction "A_A") (pintype "passive"))
      (node (ref "Q16") (pin "3") (pinfunction "C_3") (pintype "passive"))
      (node (ref "U$1") (pin "V2") (pinfunction "1_V2") (pintype "bidirectional"))
    )
    (net (code "59") (name "VCC") (class "Default")
      (node (ref "C1") (pin "+") (pinfunction "+_+") (pintype "passive"))
      (node (ref "C2") (pin "1") (pinfunction "1_1") (pintype "passive"))
      (node (ref "C5") (pin "1") (pinfunction "1_1") (pintype "passive"))
      (node (ref "C6") (pin "1") (pinfunction "1_1") (pintype "passive"))
      (node (ref "C7") (pin "1") (pinfunction "1_1") (pintype "passive"))
      (node (ref "C8") (pin "1") (pinfunction "1_1") (pintype "passive"))
      (node (ref "R1") (pin "2") (pinfunction "2_2") (pintype "passive"))
      (node (ref "R11") (pin "2") (pinfunction "2_2") (pintype "passive"))
      (node (ref "R13") (pin "2") (pinfunction "2_2") (pintype "passive"))
      (node (ref "R15") (pin "2") (pinfunction "2_2") (pintype "passive"))
      (node (ref "R17") (pin "2") (pinfunction "2_2") (pintype "passive"))
      (node (ref "R3") (pin "2") (pinfunction "2_2") (pintype "passive"))
      (node (ref "R5") (pin "2") (pinfunction "2_2") (pintype "passive"))
      (node (ref "R7") (pin "2") (pinfunction "2_2") (pintype "passive"))
      (node (ref "R9") (pin "2") (pinfunction "2_2") (pintype "passive"))
      (node (ref "U$1") (pin "A2") (pinfunction "1_A2") (pintype "bidirectional"))
    )
    (net (code "60") (name "unconnected-(E1A-I5-Pad12)") (class "Default")
      (node (ref "E1") (pin "12") (pinfunction "I5_12") (pintype "passive"))
    )
    (net (code "61") (name "unconnected-(E1A-I6-Pad11)") (class "Default")
      (node (ref "E1") (pin "11") (pinfunction "I6_11") (pintype "passive"))
    )
    (net (code "62") (name "unconnected-(E2A-I5-Pad12)") (class "Default")
      (node (ref "E2") (pin "12") (pinfunction "I5_12") (pintype "passive"))
    )
    (net (code "63") (name "unconnected-(E2A-I6-Pad11)") (class "Default")
      (node (ref "E2") (pin "11") (pinfunction "I6_11") (pintype "passive"))
    )
    (net (code "64") (name "unconnected-(E3A-I5-Pad12)") (class "Default")
      (node (ref "E3") (pin "12") (pinfunction "I5_12") (pintype "passive"))
    )
    (net (code "65") (name "unconnected-(E3A-I6-Pad11)") (class "Default")
      (node (ref "E3") (pin "11") (pinfunction "I6_11") (pintype "passive"))
    )
    (net (code "66") (name "unconnected-(E4A-I5-Pad12)") (class "Default")
      (node (ref "E4") (pin "12") (pinfunction "I5_12") (pintype "passive"))
    )
    (net (code "67") (name "unconnected-(E4A-I6-Pad11)") (class "Default")
      (node (ref "E4") (pin "11") (pinfunction "I6_11") (pintype "passive"))
    )
  )
)
